# Theia.net
KiCad netlist of a schematic drawn in EAGLE
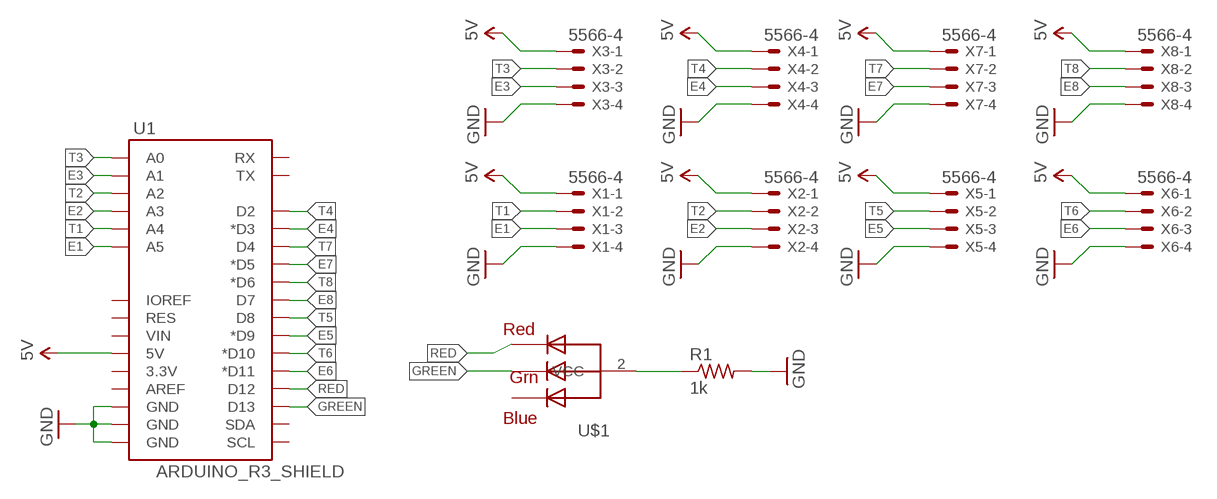
[diagram p0: schematic, sheet 1]

(export (version "E")
  (design (tool "Eeschema 10.0.6"))
  (components
    (comp (ref "R1")
      (value "1k")
      (footprint "eagle-import:0207_7")
      (libsource (lib "eagle-import") (part "R-US_0207/7"))
    )
    (comp (ref "U$1")
      (value "RGBLED_CA")
      (footprint "eagle-import:LED5MMRGB")
      (libsource (lib "eagle-import") (part "RGBLED_CA"))
    )
    (comp (ref "U1")
      (value "ARDUINO_R3_SHIELD")
      (footprint "eagle-import:UNO_R3_SHIELD")
      (libsource (lib "eagle-import") (part "ARDUINO_R3_SHIELD"))
    )
    (comp (ref "X1")
      (value "5566-4")
      (footprint "eagle-import:5566-4")
      (libsource (lib "eagle-import") (part "5566-4"))
    )
    (comp (ref "X2")
      (value "5566-4")
      (footprint "eagle-import:5566-4")
      (libsource (lib "eagle-import") (part "5566-4"))
    )
    (comp (ref "X3")
      (value "5566-4")
      (footprint "eagle-import:5566-4")
      (libsource (lib "eagle-import") (part "5566-4"))
    )
    (comp (ref "X4")
      (value "5566-4")
      (footprint "eagle-import:5566-4")
      (libsource (lib "eagle-import") (part "5566-4"))
    )
    (comp (ref "X5")
      (value "5566-4")
      (footprint "eagle-import:5566-4")
      (libsource (lib "eagle-import") (part "5566-4"))
    )
    (comp (ref "X6")
      (value "5566-4")
      (footprint "eagle-import:5566-4")
      (libsource (lib "eagle-import") (part "5566-4"))
    )
    (comp (ref "X7")
      (value "5566-4")
      (footprint "eagle-import:5566-4")
      (libsource (lib "eagle-import") (part "5566-4"))
    )
    (comp (ref "X8")
      (value "5566-4")
      (footprint "eagle-import:5566-4")
      (libsource (lib "eagle-import") (part "5566-4"))
    )
  )
  (nets
    (net (code "1") (name "5V") (class "Default")
      (node (ref "U1") (pin "5V") (pinfunction "5V_5V") (pintype "bidirectional"))
      (node (ref "X1") (pin "1") (pinfunction "S_1") (pintype "passive"))
      (node (ref "X2") (pin "1") (pinfunction "S_1") (pintype "passive"))
      (node (ref "X3") (pin "1") (pinfunction "S_1") (pintype "passive"))
      (node (ref "X4") (pin "1") (pinfunction "S_1") (pintype "passive"))
      (node (ref "X5") (pin "1") (pinfunction "S_1") (pintype "passive"))
      (node (ref "X6") (pin "1") (pinfunction "S_1") (pintype "passive"))
      (node (ref "X7") (pin "1") (pinfunction "S_1") (pintype "passive"))
      (node (ref "X8") (pin "1") (pinfunction "S_1") (pintype "passive"))
    )
    (net (code "2") (name "E1") (class "Default")
      (node (ref "U1") (pin "A5") (pinfunction "A5_A5") (pintype "bidirectional"))
      (node (ref "X1") (pin "3") (pinfunction "S_3") (pintype "passive"))
    )
    (net (code "3") (name "E2") (class "Default")
      (node (ref "U1") (pin "A3") (pinfunction "A3_A3") (pintype "bidirectional"))
      (node (ref "X2") (pin "3") (pinfunction "S_3") (pintype "passive"))
    )
    (net (code "4") (name "E3") (class "Default")
      (node (ref "U1") (pin "A1") (pinfunction "A1_A1") (pintype "bidirectional"))
      (node (ref "X3") (pin "3") (pinfunction "S_3") (pintype "passive"))
    )
    (net (code "5") (name "E4") (class "Default")
      (node (ref "U1") (pin "D3") (pinfunction "*D3_D3") (pintype "bidirectional"))
      (node (ref "X4") (pin "3") (pinfunction "S_3") (pintype "passive"))
    )
    (net (code "6") (name "E5") (class "Default")
      (node (ref "U1") (pin "D9") (pinfunction "*D9_D9") (pintype "bidirectional"))
      (node (ref "X5") (pin "3") (pinfunction "S_3") (pintype "passive"))
    )
    (net (code "7") (name "E6") (class "Default")
      (node (ref "U1") (pin "D11") (pinfunction "*D11_D11") (pintype "bidirectional"))
      (node (ref "X6") (pin "3") (pinfunction "S_3") (pintype "passive"))
    )
    (net (code "8") (name "E7") (class "Default")
      (node (ref "U1") (pin "D5") (pinfunction "*D5_D5") (pintype "bidirectional"))
      (node (ref "X7") (pin "3") (pinfunction "S_3") (pintype "passive"))
    )
    (net (code "9") (name "E8") (class "Default")
      (node (ref "U1") (pin "D7") (pinfunction "D7_D7") (pintype "bidirectional"))
      (node (ref "X8") (pin "3") (pinfunction "S_3") (pintype "passive"))
    )
    (net (code "10") (name "GND") (class "Default")
      (node (ref "R1") (pin "2") (pinfunction "2_2") (pintype "passive"))
      (node (ref "U1") (pin "GND@0") (pinfunction "GND_GND@0") (pintype "bidirectional"))
      (node (ref "U1") (pin "GND@1") (pinfunction "GND_GND@1") (pintype "bidirectional"))
      (node (ref "U1") (pin "GND@2") (pinfunction "GND_GND@2") (pintype "bidirectional"))
      (node (ref "X1") (pin "4") (pinfunction "S_4") (pintype "passive"))
      (node (ref "X2") (pin "4") (pinfunction "S_4") (pintype "passive"))
      (node (ref "X3") (pin "4") (pinfunction "S_4") (pintype "passive"))
      (node (ref "X4") (pin "4") (pinfunction "S_4") (pintype "passive"))
      (node (ref "X5") (pin "4") (pinfunction "S_4") (pintype "passive"))
      (node (ref "X6") (pin "4") (pinfunction "S_4") (pintype "passive"))
      (node (ref "X7") (pin "4") (pinfunction "S_4") (pintype "passive"))
      (node (ref "X8") (pin "4") (pinfunction "S_4") (pintype "passive"))
    )
    (net (code "11") (name "GREEN") (class "Default")
      (node (ref "U$1") (pin "3") (pinfunction "GREEN_3") (pintype "bidirectional"))
      (node (ref "U1") (pin "D13") (pinfunction "D13_D13") (pintype "bidirectional"))
    )
    (net (code "12") (name "Net-(U$1-VCC)") (class "Default")
      (node (ref "R1") (pin "1") (pinfunction "1_1") (pintype "passive"))
      (node (ref "U$1") (pin "2") (pinfunction "VCC_2") (pintype "bidirectional"))
    )
    (net (code "13") (name "RED") (class "Default")
      (node (ref "U$1") (pin "1") (pinfunction "RED_1") (pintype "bidirectional"))
      (node (ref "U1") (pin "D12") (pinfunction "D12_D12") (pintype "bidirectional"))
    )
    (net (code "14") (name "T1") (class "Default")
      (node (ref "U1") (pin "A4") (pinfunction "A4_A4") (pintype "bidirectional"))
      (node (ref "X1") (pin "2") (pinfunction "S_2") (pintype "passive"))
    )
    (net (code "15") (name "T2") (class "Default")
      (node (ref "U1") (pin "A2") (pinfunction "A2_A2") (pintype "bidirectional"))
      (node (ref "X2") (pin "2") (pinfunction "S_2") (pintype "passive"))
    )
    (net (code "16") (name "T3") (class "Default")
      (node (ref "U1") (pin "A0") (pinfunction "A0_A0") (pintype "bidirectional"))
      (node (ref "X3") (pin "2") (pinfunction "S_2") (pintype "passive"))
    )
    (net (code "17") (name "T4") (class "Default")
      (node (ref "U1") (pin "D2") (pinfunction "D2_D2") (pintype "bidirectional"))
      (node (ref "X4") (pin "2") (pinfunction "S_2") (pintype "passive"))
    )
    (net (code "18") (name "T5") (class "Default")
      (node (ref "U1") (pin "D8") (pinfunction "D8_D8") (pintype "bidirectional"))
      (node (ref "X5") (pin "2") (pinfunction "S_2") (pintype "passive"))
    )
    (net (code "19") (name "T6") (class "Default")
      (node (ref "U1") (pin "D10") (pinfunction "*D10_D10") (pintype "bidirectional"))
      (node (ref "X6") (pin "2") (pinfunction "S_2") (pintype "passive"))
    )
    (net (code "20") (name "T7") (class "Default")
      (node (ref "U1") (pin "D4") (pinfunction "D4_D4") (pintype "bidirectional"))
      (node (ref "X7") (pin "2") (pinfunction "S_2") (pintype "passive"))
    )
    (net (code "21") (name "T8") (class "Default")
      (node (ref "U1") (pin "D6") (pinfunction "*D6_D6") (pintype "bidirectional"))
      (node (ref "X8") (pin "2") (pinfunction "S_2") (pintype "passive"))
    )
    (net (code "22") (name "unconnected-(U$1-BLUE-Pad4)") (class "Default")
      (node (ref "U$1") (pin "4") (pinfunction "BLUE_4") (pintype "bidirectional"))
    )
    (net (code "23") (name "unconnected-(U1-Pad3.3V)") (class "Default")
      (node (ref "U1") (pin "3.3V") (pinfunction "3.3V_3.3V") (pintype "bidirectional"))
    )
    (net (code "24") (name "unconnected-(U1-PadAREF)") (class "Default")
      (node (ref "U1") (pin "AREF") (pinfunction "AREF_AREF") (pintype "bidirectional"))
    )
    (net (code "25") (name "unconnected-(U1-PadIOREF)") (class "Default")
      (node (ref "U1") (pin "IOREF") (pinfunction "IOREF_IOREF") (pintype "bidirectional"))
    )
    (net (code "26") (name "unconnected-(U1-PadRES)") (class "Default")
      (node (ref "U1") (pin "RES") (pinfunction "RES_RES") (pintype "bidirectional"))
    )
    (net (code "27") (name "unconnected-(U1-PadRX)") (class "Default")
      (node (ref "U1") (pin "RX") (pinfunction "RX_RX") (pintype "bidirectional"))
    )
    (net (code "28") (name "unconnected-(U1-PadSCL)") (class "Default")
      (node (ref "U1") (pin "SCL") (pinfunction "SCL_SCL") (pintype "bidirectional"))
    )
    (net (code "29") (name "unconnected-(U1-PadSDA)") (class "Default")
      (node (ref "U1") (pin "SDA") (pinfunction "SDA_SDA") (pintype "bidirectional"))
    )
    (net (code "30") (name "unconnected-(U1-PadTX)") (class "Default")
      (node (ref "U1") (pin "TX") (pinfunction "TX_TX") (pintype "bidirectional"))
    )
    (net (code "31") (name "unconnected-(U1-PadVIN)") (class "Default")
      (node (ref "U1") (pin "VIN") (pinfunction "VIN_VIN") (pintype "bidirectional"))
    )
  )
)
